# finalPCB2.net
KiCad netlist of a schematic drawn in EAGLE
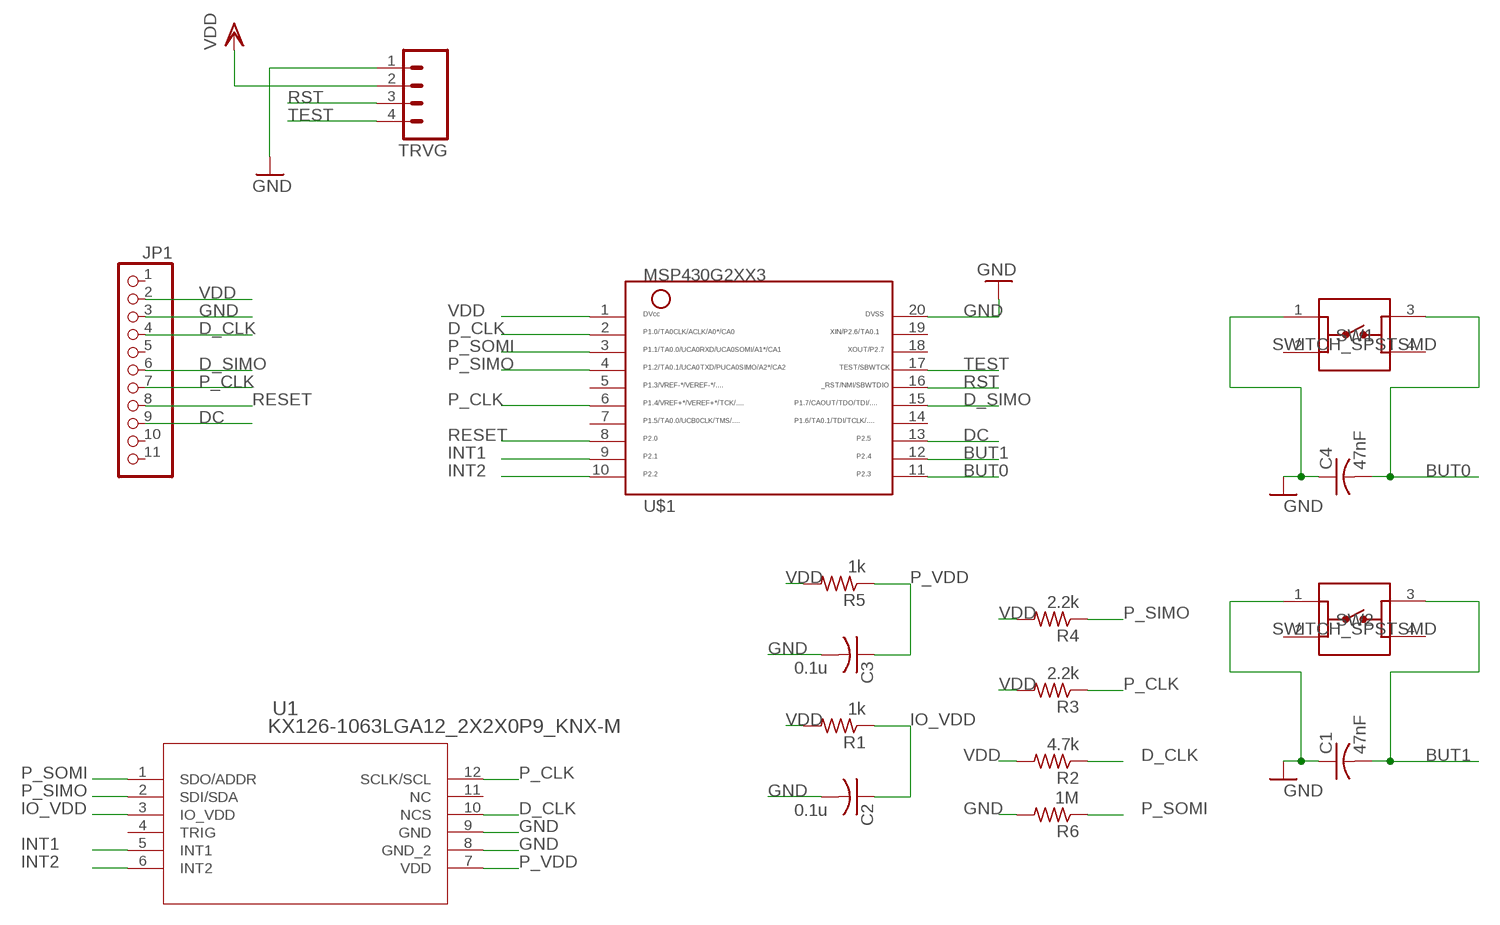
[diagram p0: schematic, sheet 1]

(export (version "E")
  (design (tool "Eeschema 10.0.6"))
  (components
    (comp (ref "C1")
      (value "47nF")
      (footprint "eagle-import:C0603")
      (libsource (lib "eagle-import") (part "C-USC0603"))
    )
    (comp (ref "C2")
      (value "0.1u")
      (footprint "eagle-import:C0603")
      (libsource (lib "eagle-import") (part "C-USC0603"))
    )
    (comp (ref "C3")
      (value "0.1u")
      (footprint "eagle-import:C0603")
      (libsource (lib "eagle-import") (part "C-USC0603"))
    )
    (comp (ref "C4")
      (value "47nF")
      (footprint "eagle-import:C0603")
      (libsource (lib "eagle-import") (part "C-USC0603"))
    )
    (comp (ref "JP1")
      (value "HEADER-1X11")
      (footprint "eagle-import:1X11_ROUND")
      (libsource (lib "eagle-import") (part "HEADER-1X11"))
    )
    (comp (ref "R1")
      (value "1k")
      (footprint "eagle-import:R0402")
      (libsource (lib "eagle-import") (part "R-US_R0402"))
    )
    (comp (ref "R2")
      (value "4.7k")
      (footprint "eagle-import:R0402")
      (libsource (lib "eagle-import") (part "R-US_R0402"))
    )
    (comp (ref "R3")
      (value "2.2k")
      (footprint "eagle-import:R0402")
      (libsource (lib "eagle-import") (part "R-US_R0402"))
    )
    (comp (ref "R4")
      (value "2.2k")
      (footprint "eagle-import:R0402")
      (libsource (lib "eagle-import") (part "R-US_R0402"))
    )
    (comp (ref "R5")
      (value "1k")
      (footprint "eagle-import:R0402")
      (libsource (lib "eagle-import") (part "R-US_R0402"))
    )
    (comp (ref "R6")
      (value "1M")
      (footprint "eagle-import:R0402")
      (libsource (lib "eagle-import") (part "R-US_R0402"))
    )
    (comp (ref "SW1")
      (value "SWITCH_SPSTSMD")
      (footprint "eagle-import:SW_1571563-4")
      (libsource (lib "eagle-import") (part "SWITCH_SPSTSMD"))
    )
    (comp (ref "SW2")
      (value "SWITCH_SPSTSMD")
      (footprint "eagle-import:SW_1571563-4")
      (libsource (lib "eagle-import") (part "SWITCH_SPSTSMD"))
    )
    (comp (ref "TRVG")
      (value "M04LOCK")
      (footprint "eagle-import:1X04_LOCK")
      (libsource (lib "eagle-import") (part "M04LOCK"))
    )
    (comp (ref "U$1")
      (value "MSP430G2XX3TSSOP")
      (footprint "eagle-import:PW20")
      (libsource (lib "eagle-import") (part "MSP430G2XX3TSSOP"))
    )
    (comp (ref "U1")
      (value "KX126-1063LGA12_2X2X0P9_KNX-M")
      (footprint "eagle-import:LGA12_2X2X0P9_KNX-M")
      (fields
        (field (name "MANUFACTURER_PART_NUMBER") "KX126-1063")
        (field (name "COPYRIGHT") "Copyright (C) 2021 Ultra Librarian. All rights reserved.")
      )
      (libsource (lib "eagle-import") (part "KX126-1063LGA12_2X2X0P9_KNX-M"))
    )
  )
  (nets
    (net (code "1") (name "/BUT0") (class "Default")
      (node (ref "C4") (pin "2") (pinfunction "2_2") (pintype "passive"))
      (node (ref "SW1") (pin "3") (pinfunction "3_3") (pintype "passive"))
      (node (ref "U$1") (pin "11") (pinfunction "11_11") (pintype "bidirectional"))
    )
    (net (code "2") (name "/BUT1") (class "Default")
      (node (ref "C1") (pin "2") (pinfunction "2_2") (pintype "passive"))
      (node (ref "SW2") (pin "3") (pinfunction "3_3") (pintype "passive"))
      (node (ref "U$1") (pin "12") (pinfunction "12_12") (pintype "bidirectional"))
    )
    (net (code "3") (name "/DC") (class "Default")
      (node (ref "JP1") (pin "9") (pinfunction "9_9") (pintype "passive"))
      (node (ref "U$1") (pin "13") (pinfunction "13_13") (pintype "bidirectional"))
    )
    (net (code "4") (name "/D_CLK") (class "Default")
      (node (ref "JP1") (pin "4") (pinfunction "4_4") (pintype "passive"))
      (node (ref "R2") (pin "1") (pinfunction "1_1") (pintype "passive"))
      (node (ref "U$1") (pin "2") (pinfunction "2_2") (pintype "bidirectional"))
      (node (ref "U1") (pin "10") (pinfunction "NCS_10") (pintype "input"))
    )
    (net (code "5") (name "/D_SIMO") (class "Default")
      (node (ref "JP1") (pin "6") (pinfunction "6_6") (pintype "passive"))
      (node (ref "U$1") (pin "15") (pinfunction "15_15") (pintype "bidirectional"))
    )
    (net (code "6") (name "/INT1") (class "Default")
      (node (ref "U$1") (pin "9") (pinfunction "9_9") (pintype "bidirectional"))
      (node (ref "U1") (pin "5") (pinfunction "INT1_5") (pintype "output"))
    )
    (net (code "7") (name "/INT2") (class "Default")
      (node (ref "U$1") (pin "10") (pinfunction "10_10") (pintype "bidirectional"))
      (node (ref "U1") (pin "6") (pinfunction "INT2_6") (pintype "output"))
    )
    (net (code "8") (name "/IO_VDD") (class "Default")
      (node (ref "C2") (pin "1") (pinfunction "1_1") (pintype "passive"))
      (node (ref "R1") (pin "1") (pinfunction "1_1") (pintype "passive"))
      (node (ref "U1") (pin "3") (pinfunction "IO_VDD_3") (pintype "power_in"))
    )
    (net (code "9") (name "/P_CLK") (class "Default")
      (node (ref "JP1") (pin "7") (pinfunction "7_7") (pintype "passive"))
      (node (ref "R3") (pin "1") (pinfunction "1_1") (pintype "passive"))
      (node (ref "U$1") (pin "6") (pinfunction "6_6") (pintype "bidirectional"))
      (node (ref "U1") (pin "12") (pinfunction "SCLK/SCL_12") (pintype "input"))
    )
    (net (code "10") (name "/P_SIMO") (class "Default")
      (node (ref "R4") (pin "1") (pinfunction "1_1") (pintype "passive"))
      (node (ref "U$1") (pin "4") (pinfunction "4_4") (pintype "bidirectional"))
      (node (ref "U1") (pin "2") (pinfunction "SDI/SDA_2") (pintype "input"))
    )
    (net (code "11") (name "/P_SOMI") (class "Default")
      (node (ref "R6") (pin "1") (pinfunction "1_1") (pintype "passive"))
      (node (ref "U$1") (pin "3") (pinfunction "3_3") (pintype "bidirectional"))
      (node (ref "U1") (pin "1") (pinfunction "SDO/ADDR_1") (pintype "input"))
    )
    (net (code "12") (name "/P_VDD") (class "Default")
      (node (ref "C3") (pin "1") (pinfunction "1_1") (pintype "passive"))
      (node (ref "R5") (pin "1") (pinfunction "1_1") (pintype "passive"))
      (node (ref "U1") (pin "7") (pinfunction "VDD_7") (pintype "power_in"))
    )
    (net (code "13") (name "/RESET") (class "Default")
      (node (ref "JP1") (pin "8") (pinfunction "8_8") (pintype "passive"))
      (node (ref "U$1") (pin "8") (pinfunction "8_8") (pintype "bidirectional"))
    )
    (net (code "14") (name "/RST") (class "Default")
      (node (ref "TRVG") (pin "3") (pinfunction "3_3") (pintype "passive"))
      (node (ref "U$1") (pin "16") (pinfunction "16_16") (pintype "bidirectional"))
    )
    (net (code "15") (name "/TEST") (class "Default")
      (node (ref "TRVG") (pin "4") (pinfunction "4_4") (pintype "passive"))
      (node (ref "U$1") (pin "17") (pinfunction "17_17") (pintype "bidirectional"))
    )
    (net (code "16") (name "GND") (class "Default")
      (node (ref "C1") (pin "1") (pinfunction "1_1") (pintype "passive"))
      (node (ref "C2") (pin "2") (pinfunction "2_2") (pintype "passive"))
      (node (ref "C3") (pin "2") (pinfunction "2_2") (pintype "passive"))
      (node (ref "C4") (pin "1") (pinfunction "1_1") (pintype "passive"))
      (node (ref "JP1") (pin "3") (pinfunction "3_3") (pintype "passive"))
      (node (ref "R6") (pin "2") (pinfunction "2_2") (pintype "passive"))
      (node (ref "SW1") (pin "1") (pinfunction "1_1") (pintype "passive"))
      (node (ref "SW2") (pin "1") (pinfunction "1_1") (pintype "passive"))
      (node (ref "TRVG") (pin "1") (pinfunction "1_1") (pintype "passive"))
      (node (ref "U$1") (pin "20") (pinfunction "20_20") (pintype "bidirectional"))
      (node (ref "U1") (pin "8") (pinfunction "GND_2_8") (pintype "passive"))
      (node (ref "U1") (pin "9") (pinfunction "GND_9") (pintype "passive"))
    )
    (net (code "17") (name "VDD") (class "Default")
      (node (ref "JP1") (pin "2") (pinfunction "2_2") (pintype "passive"))
      (node (ref "R1") (pin "2") (pinfunction "2_2") (pintype "passive"))
      (node (ref "R2") (pin "2") (pinfunction "2_2") (pintype "passive"))
      (node (ref "R3") (pin "2") (pinfunction "2_2") (pintype "passive"))
      (node (ref "R4") (pin "2") (pinfunction "2_2") (pintype "passive"))
      (node (ref "R5") (pin "2") (pinfunction "2_2") (pintype "passive"))
      (node (ref "TRVG") (pin "2") (pinfunction "2_2") (pintype "passive"))
      (node (ref "U$1") (pin "1") (pinfunction "1_1") (pintype "bidirectional"))
    )
    (net (code "18") (name "unconnected-(JP1-Pad1)") (class "Default")
      (node (ref "JP1") (pin "1") (pinfunction "1_1") (pintype "passive"))
    )
    (net (code "19") (name "unconnected-(JP1-Pad5)") (class "Default")
      (node (ref "JP1") (pin "5") (pinfunction "5_5") (pintype "passive"))
    )
    (net (code "20") (name "unconnected-(JP1-Pad10)") (class "Default")
      (node (ref "JP1") (pin "10") (pinfunction "10_10") (pintype "passive"))
    )
    (net (code "21") (name "unconnected-(JP1-Pad11)") (class "Default")
      (node (ref "JP1") (pin "11") (pinfunction "11_11") (pintype "passive"))
    )
    (net (code "22") (name "unconnected-(SW1-Pad2)") (class "Default")
      (node (ref "SW1") (pin "2") (pinfunction "2_2") (pintype "passive"))
    )
    (net (code "23") (name "unconnected-(SW1-Pad4)") (class "Default")
      (node (ref "SW1") (pin "4") (pinfunction "4_4") (pintype "passive"))
    )
    (net (code "24") (name "unconnected-(SW2-Pad2)") (class "Default")
      (node (ref "SW2") (pin "2") (pinfunction "2_2") (pintype "passive"))
    )
    (net (code "25") (name "unconnected-(SW2-Pad4)") (class "Default")
      (node (ref "SW2") (pin "4") (pinfunction "4_4") (pintype "passive"))
    )
    (net (code "26") (name "unconnected-(U$1-Pad5)") (class "Default")
      (node (ref "U$1") (pin "5") (pinfunction "5_5") (pintype "bidirectional"))
    )
    (net (code "27") (name "unconnected-(U$1-Pad7)") (class "Default")
      (node (ref "U$1") (pin "7") (pinfunction "7_7") (pintype "bidirectional"))
    )
    (net (code "28") (name "unconnected-(U$1-Pad14)") (class "Default")
      (node (ref "U$1") (pin "14") (pinfunction "14_14") (pintype "bidirectional"))
    )
    (net (code "29") (name "unconnected-(U$1-Pad18)") (class "Default")
      (node (ref "U$1") (pin "18") (pinfunction "18_18") (pintype "bidirectional"))
    )
    (net (code "30") (name "unconnected-(U$1-Pad19)") (class "Default")
      (node (ref "U$1") (pin "19") (pinfunction "19_19") (pintype "bidirectional"))
    )
    (net (code "31") (name "unconnected-(U1-NC-Pad11)") (class "Default")
      (node (ref "U1") (pin "11") (pinfunction "NC_11") (pintype "no_connect"))
    )
    (net (code "32") (name "unconnected-(U1-TRIG-Pad4)") (class "Default")
      (node (ref "U1") (pin "4") (pinfunction "TRIG_4") (pintype "input"))
    )
  )
)
